# jupiter6-filter.net
KiCad netlist of a schematic drawn in EAGLE
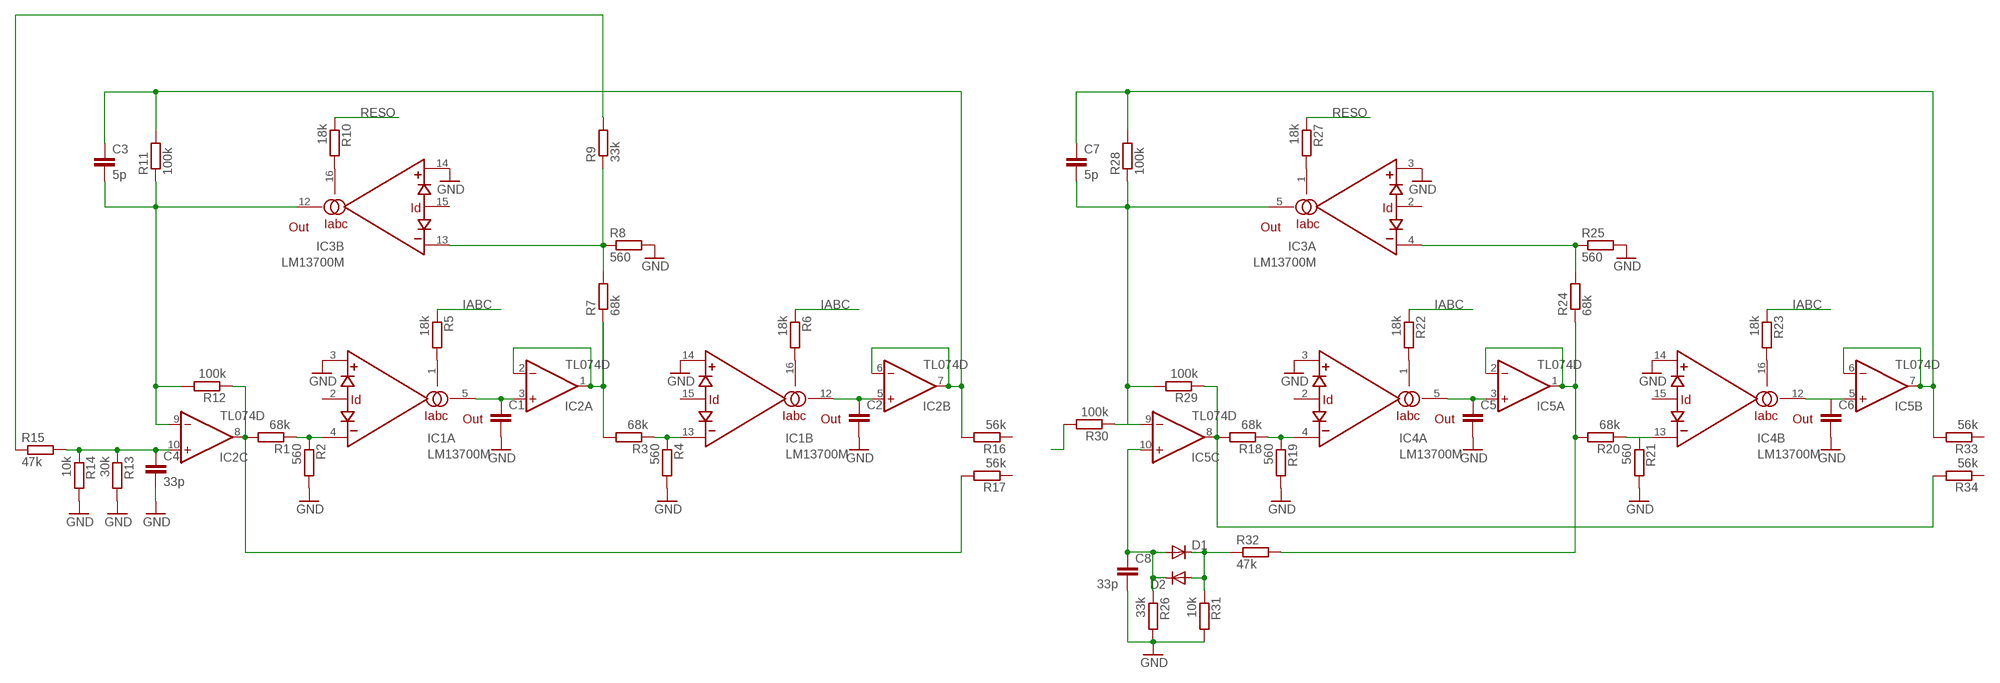
[diagram p0: schematic, sheet 1]

(export (version "E")
  (design (tool "Eeschema 10.0.6"))
  (components
    (comp (ref "C1")
      (value "C-EUC0603")
      (footprint "eagle-import:C0603")
      (libsource (lib "eagle-import") (part "C-EUC0603"))
    )
    (comp (ref "C2")
      (value "C-EUC0603")
      (footprint "eagle-import:C0603")
      (libsource (lib "eagle-import") (part "C-EUC0603"))
    )
    (comp (ref "C3")
      (value "5p")
      (footprint "eagle-import:C0603")
      (libsource (lib "eagle-import") (part "C-EUC0603"))
    )
    (comp (ref "C4")
      (value "33p")
      (footprint "eagle-import:C0603")
      (libsource (lib "eagle-import") (part "C-EUC0603"))
    )
    (comp (ref "C5")
      (value "C-EUC0603")
      (footprint "eagle-import:C0603")
      (libsource (lib "eagle-import") (part "C-EUC0603"))
    )
    (comp (ref "C6")
      (value "C-EUC0603")
      (footprint "eagle-import:C0603")
      (libsource (lib "eagle-import") (part "C-EUC0603"))
    )
    (comp (ref "C7")
      (value "5p")
      (footprint "eagle-import:C0603")
      (libsource (lib "eagle-import") (part "C-EUC0603"))
    )
    (comp (ref "C8")
      (value "33p")
      (footprint "eagle-import:C0603")
      (libsource (lib "eagle-import") (part "C-EUC0603"))
    )
    (comp (ref "D1")
      (value "DIODE-SOD80C")
      (footprint "eagle-import:SOD80C")
      (libsource (lib "eagle-import") (part "DIODE-SOD80C"))
    )
    (comp (ref "D2")
      (value "DIODE-SOD80C")
      (footprint "eagle-import:SOD80C")
      (libsource (lib "eagle-import") (part "DIODE-SOD80C"))
    )
    (comp (ref "IC1")
      (value "LM13700M")
      (footprint "eagle-import:SO16")
      (libsource (lib "eagle-import") (part "LM13700M"))
    )
    (comp (ref "IC2")
      (value "TL074D")
      (footprint "eagle-import:SO14")
      (libsource (lib "eagle-import") (part "TL074D"))
    )
    (comp (ref "IC3")
      (value "LM13700M")
      (footprint "eagle-import:SO16")
      (libsource (lib "eagle-import") (part "LM13700M"))
    )
    (comp (ref "IC4")
      (value "LM13700M")
      (footprint "eagle-import:SO16")
      (libsource (lib "eagle-import") (part "LM13700M"))
    )
    (comp (ref "IC5")
      (value "TL074D")
      (footprint "eagle-import:SO14")
      (libsource (lib "eagle-import") (part "TL074D"))
    )
    (comp (ref "R1")
      (value "68k")
      (footprint "eagle-import:R0603")
      (libsource (lib "eagle-import") (part "R-EU_R0603"))
    )
    (comp (ref "R2")
      (value "560")
      (footprint "eagle-import:R0603")
      (libsource (lib "eagle-import") (part "R-EU_R0603"))
    )
    (comp (ref "R3")
      (value "68k")
      (footprint "eagle-import:R0603")
      (libsource (lib "eagle-import") (part "R-EU_R0603"))
    )
    (comp (ref "R4")
      (value "560")
      (footprint "eagle-import:R0603")
      (libsource (lib "eagle-import") (part "R-EU_R0603"))
    )
    (comp (ref "R5")
      (value "18k")
      (footprint "eagle-import:R0603")
      (libsource (lib "eagle-import") (part "R-EU_R0603"))
    )
    (comp (ref "R6")
      (value "18k")
      (footprint "eagle-import:R0603")
      (libsource (lib "eagle-import") (part "R-EU_R0603"))
    )
    (comp (ref "R7")
      (value "68k")
      (footprint "eagle-import:R0603")
      (libsource (lib "eagle-import") (part "R-EU_R0603"))
    )
    (comp (ref "R8")
      (value "560")
      (footprint "eagle-import:R0603")
      (libsource (lib "eagle-import") (part "R-EU_R0603"))
    )
    (comp (ref "R9")
      (value "33k")
      (footprint "eagle-import:R0603")
      (libsource (lib "eagle-import") (part "R-EU_R0603"))
    )
    (comp (ref "R10")
      (value "18k")
      (footprint "eagle-import:R0603")
      (libsource (lib "eagle-import") (part "R-EU_R0603"))
    )
    (comp (ref "R11")
      (value "100k")
      (footprint "eagle-import:R0603")
      (libsource (lib "eagle-import") (part "R-EU_R0603"))
    )
    (comp (ref "R12")
      (value "100k")
      (footprint "eagle-import:R0603")
      (libsource (lib "eagle-import") (part "R-EU_R0603"))
    )
    (comp (ref "R13")
      (value "30k")
      (footprint "eagle-import:R0603")
      (libsource (lib "eagle-import") (part "R-EU_R0603"))
    )
    (comp (ref "R14")
      (value "10k")
      (footprint "eagle-import:R0603")
      (libsource (lib "eagle-import") (part "R-EU_R0603"))
    )
    (comp (ref "R15")
      (value "47k")
      (footprint "eagle-import:R0603")
      (libsource (lib "eagle-import") (part "R-EU_R0603"))
    )
    (comp (ref "R16")
      (value "56k")
      (footprint "eagle-import:R0603")
      (libsource (lib "eagle-import") (part "R-EU_R0603"))
    )
    (comp (ref "R17")
      (value "56k")
      (footprint "eagle-import:R0603")
      (libsource (lib "eagle-import") (part "R-EU_R0603"))
    )
    (comp (ref "R18")
      (value "68k")
      (footprint "eagle-import:R0603")
      (libsource (lib "eagle-import") (part "R-EU_R0603"))
    )
    (comp (ref "R19")
      (value "560")
      (footprint "eagle-import:R0603")
      (libsource (lib "eagle-import") (part "R-EU_R0603"))
    )
    (comp (ref "R20")
      (value "68k")
      (footprint "eagle-import:R0603")
      (libsource (lib "eagle-import") (part "R-EU_R0603"))
    )
    (comp (ref "R21")
      (value "560")
      (footprint "eagle-import:R0603")
      (libsource (lib "eagle-import") (part "R-EU_R0603"))
    )
    (comp (ref "R22")
      (value "18k")
      (footprint "eagle-import:R0603")
      (libsource (lib "eagle-import") (part "R-EU_R0603"))
    )
    (comp (ref "R23")
      (value "18k")
      (footprint "eagle-import:R0603")
      (libsource (lib "eagle-import") (part "R-EU_R0603"))
    )
    (comp (ref "R24")
      (value "68k")
      (footprint "eagle-import:R0603")
      (libsource (lib "eagle-import") (part "R-EU_R0603"))
    )
    (comp (ref "R25")
      (value "560")
      (footprint "eagle-import:R0603")
      (libsource (lib "eagle-import") (part "R-EU_R0603"))
    )
    (comp (ref "R26")
      (value "33k")
      (footprint "eagle-import:R0603")
      (libsource (lib "eagle-import") (part "R-EU_R0603"))
    )
    (comp (ref "R27")
      (value "18k")
      (footprint "eagle-import:R0603")
      (libsource (lib "eagle-import") (part "R-EU_R0603"))
    )
    (comp (ref "R28")
      (value "100k")
      (footprint "eagle-import:R0603")
      (libsource (lib "eagle-import") (part "R-EU_R0603"))
    )
    (comp (ref "R29")
      (value "100k")
      (footprint "eagle-import:R0603")
      (libsource (lib "eagle-import") (part "R-EU_R0603"))
    )
    (comp (ref "R30")
      (value "100k")
      (footprint "eagle-import:R0603")
      (libsource (lib "eagle-import") (part "R-EU_R0603"))
    )
    (comp (ref "R31")
      (value "10k")
      (footprint "eagle-import:R0603")
      (libsource (lib "eagle-import") (part "R-EU_R0603"))
    )
    (comp (ref "R32")
      (value "47k")
      (footprint "eagle-import:R0603")
      (libsource (lib "eagle-import") (part "R-EU_R0603"))
    )
    (comp (ref "R33")
      (value "56k")
      (footprint "eagle-import:R0603")
      (libsource (lib "eagle-import") (part "R-EU_R0603"))
    )
    (comp (ref "R34")
      (value "56k")
      (footprint "eagle-import:R0603")
      (libsource (lib "eagle-import") (part "R-EU_R0603"))
    )
  )
  (nets
    (net (code "1") (name "/IABC") (class "Default")
      (node (ref "R22") (pin "1") (pinfunction "1_1") (pintype "passive"))
      (node (ref "R23") (pin "1") (pinfunction "1_1") (pintype "passive"))
      (node (ref "R5") (pin "1") (pinfunction "1_1") (pintype "passive"))
      (node (ref "R6") (pin "1") (pinfunction "1_1") (pintype "passive"))
    )
    (net (code "2") (name "/RESO") (class "Default")
      (node (ref "R10") (pin "1") (pinfunction "1_1") (pintype "passive"))
      (node (ref "R27") (pin "1") (pinfunction "1_1") (pintype "passive"))
    )
    (net (code "3") (name "GND") (class "Default")
      (node (ref "C1") (pin "2") (pinfunction "2_2") (pintype "passive"))
      (node (ref "C2") (pin "2") (pinfunction "2_2") (pintype "passive"))
      (node (ref "C4") (pin "2") (pinfunction "2_2") (pintype "passive"))
      (node (ref "C5") (pin "2") (pinfunction "2_2") (pintype "passive"))
      (node (ref "C6") (pin "2") (pinfunction "2_2") (pintype "passive"))
      (node (ref "C8") (pin "2") (pinfunction "2_2") (pintype "passive"))
      (node (ref "IC1") (pin "14") (pinfunction "+IN_14") (pintype "bidirectional"))
      (node (ref "IC1") (pin "3") (pinfunction "+IN_3") (pintype "bidirectional"))
      (node (ref "IC3") (pin "14") (pinfunction "+IN_14") (pintype "bidirectional"))
      (node (ref "IC3") (pin "3") (pinfunction "+IN_3") (pintype "bidirectional"))
      (node (ref "IC4") (pin "14") (pinfunction "+IN_14") (pintype "bidirectional"))
      (node (ref "IC4") (pin "3") (pinfunction "+IN_3") (pintype "bidirectional"))
      (node (ref "R13") (pin "2") (pinfunction "2_2") (pintype "passive"))
      (node (ref "R14") (pin "2") (pinfunction "2_2") (pintype "passive"))
      (node (ref "R19") (pin "2") (pinfunction "2_2") (pintype "passive"))
      (node (ref "R2") (pin "2") (pinfunction "2_2") (pintype "passive"))
      (node (ref "R21") (pin "2") (pinfunction "2_2") (pintype "passive"))
      (node (ref "R25") (pin "2") (pinfunction "2_2") (pintype "passive"))
      (node (ref "R26") (pin "2") (pinfunction "2_2") (pintype "passive"))
      (node (ref "R31") (pin "2") (pinfunction "2_2") (pintype "passive"))
      (node (ref "R4") (pin "2") (pinfunction "2_2") (pintype "passive"))
      (node (ref "R8") (pin "2") (pinfunction "2_2") (pintype "passive"))
    )
    (net (code "4") (name "Net-(D1-PadC)") (class "Default")
      (node (ref "D1") (pin "C") (pinfunction "C_C") (pintype "passive"))
      (node (ref "D2") (pin "A") (pinfunction "A_A") (pintype "passive"))
      (node (ref "R31") (pin "1") (pinfunction "1_1") (pintype "passive"))
      (node (ref "R32") (pin "1") (pinfunction "1_1") (pintype "passive"))
    )
    (net (code "5") (name "Net-(IC1A--IN)") (class "Default")
      (node (ref "IC1") (pin "4") (pinfunction "-IN_4") (pintype "bidirectional"))
      (node (ref "R1") (pin "1") (pinfunction "1_1") (pintype "passive"))
      (node (ref "R2") (pin "1") (pinfunction "1_1") (pintype "passive"))
    )
    (net (code "6") (name "Net-(IC1A-IABC)") (class "Default")
      (node (ref "IC1") (pin "1") (pinfunction "IABC_1") (pintype "bidirectional"))
      (node (ref "R5") (pin "2") (pinfunction "2_2") (pintype "passive"))
    )
    (net (code "7") (name "Net-(IC1A-OUT)") (class "Default")
      (node (ref "C1") (pin "1") (pinfunction "1_1") (pintype "passive"))
      (node (ref "IC1") (pin "5") (pinfunction "OUT_5") (pintype "bidirectional"))
      (node (ref "IC2") (pin "3") (pinfunction "+IN_3") (pintype "input"))
    )
    (net (code "8") (name "Net-(IC1B--IN)") (class "Default")
      (node (ref "IC1") (pin "13") (pinfunction "-IN_13") (pintype "bidirectional"))
      (node (ref "R3") (pin "1") (pinfunction "1_1") (pintype "passive"))
      (node (ref "R4") (pin "1") (pinfunction "1_1") (pintype "passive"))
    )
    (net (code "9") (name "Net-(IC1B-IABC)") (class "Default")
      (node (ref "IC1") (pin "16") (pinfunction "IABC_16") (pintype "bidirectional"))
      (node (ref "R6") (pin "2") (pinfunction "2_2") (pintype "passive"))
    )
    (net (code "10") (name "Net-(IC1B-OUT)") (class "Default")
      (node (ref "C2") (pin "1") (pinfunction "1_1") (pintype "passive"))
      (node (ref "IC1") (pin "12") (pinfunction "OUT_12") (pintype "bidirectional"))
      (node (ref "IC2") (pin "5") (pinfunction "+IN_5") (pintype "input"))
    )
    (net (code "11") (name "Net-(IC2A--IN)") (class "Default")
      (node (ref "IC2") (pin "1") (pinfunction "OUT_1") (pintype "output"))
      (node (ref "IC2") (pin "2") (pinfunction "-IN_2") (pintype "input"))
      (node (ref "R3") (pin "2") (pinfunction "2_2") (pintype "passive"))
      (node (ref "R7") (pin "1") (pinfunction "1_1") (pintype "passive"))
    )
    (net (code "12") (name "Net-(IC2B--IN)") (class "Default")
      (node (ref "C3") (pin "1") (pinfunction "1_1") (pintype "passive"))
      (node (ref "IC2") (pin "6") (pinfunction "-IN_6") (pintype "input"))
      (node (ref "IC2") (pin "7") (pinfunction "OUT_7") (pintype "output"))
      (node (ref "R11") (pin "2") (pinfunction "2_2") (pintype "passive"))
      (node (ref "R16") (pin "2") (pinfunction "2_2") (pintype "passive"))
    )
    (net (code "13") (name "Net-(IC2C-+IN)") (class "Default")
      (node (ref "C4") (pin "1") (pinfunction "1_1") (pintype "passive"))
      (node (ref "IC2") (pin "10") (pinfunction "+IN_10") (pintype "input"))
      (node (ref "R13") (pin "1") (pinfunction "1_1") (pintype "passive"))
      (node (ref "R14") (pin "1") (pinfunction "1_1") (pintype "passive"))
      (node (ref "R15") (pin "2") (pinfunction "2_2") (pintype "passive"))
    )
    (net (code "14") (name "Net-(IC2C--IN)") (class "Default")
      (node (ref "C3") (pin "2") (pinfunction "2_2") (pintype "passive"))
      (node (ref "IC2") (pin "9") (pinfunction "-IN_9") (pintype "input"))
      (node (ref "IC3") (pin "12") (pinfunction "OUT_12") (pintype "bidirectional"))
      (node (ref "R11") (pin "1") (pinfunction "1_1") (pintype "passive"))
      (node (ref "R12") (pin "2") (pinfunction "2_2") (pintype "passive"))
    )
    (net (code "15") (name "Net-(IC2C-OUT)") (class "Default")
      (node (ref "IC2") (pin "8") (pinfunction "OUT_8") (pintype "output"))
      (node (ref "R1") (pin "2") (pinfunction "2_2") (pintype "passive"))
      (node (ref "R12") (pin "1") (pinfunction "1_1") (pintype "passive"))
      (node (ref "R17") (pin "2") (pinfunction "2_2") (pintype "passive"))
    )
    (net (code "16") (name "Net-(IC3A--IN)") (class "Default")
      (node (ref "IC3") (pin "4") (pinfunction "-IN_4") (pintype "bidirectional"))
      (node (ref "R24") (pin "2") (pinfunction "2_2") (pintype "passive"))
      (node (ref "R25") (pin "1") (pinfunction "1_1") (pintype "passive"))
    )
    (net (code "17") (name "Net-(IC3A-IABC)") (class "Default")
      (node (ref "IC3") (pin "1") (pinfunction "IABC_1") (pintype "bidirectional"))
      (node (ref "R27") (pin "2") (pinfunction "2_2") (pintype "passive"))
    )
    (net (code "18") (name "Net-(IC3A-OUT)") (class "Default")
      (node (ref "C7") (pin "2") (pinfunction "2_2") (pintype "passive"))
      (node (ref "IC3") (pin "5") (pinfunction "OUT_5") (pintype "bidirectional"))
      (node (ref "IC5") (pin "9") (pinfunction "-IN_9") (pintype "input"))
      (node (ref "R28") (pin "1") (pinfunction "1_1") (pintype "passive"))
      (node (ref "R29") (pin "2") (pinfunction "2_2") (pintype "passive"))
      (node (ref "R30") (pin "1") (pinfunction "1_1") (pintype "passive"))
    )
    (net (code "19") (name "Net-(IC3B--IN)") (class "Default")
      (node (ref "IC3") (pin "13") (pinfunction "-IN_13") (pintype "bidirectional"))
      (node (ref "R7") (pin "2") (pinfunction "2_2") (pintype "passive"))
      (node (ref "R8") (pin "1") (pinfunction "1_1") (pintype "passive"))
      (node (ref "R9") (pin "1") (pinfunction "1_1") (pintype "passive"))
    )
    (net (code "20") (name "Net-(IC3B-IABC)") (class "Default")
      (node (ref "IC3") (pin "16") (pinfunction "IABC_16") (pintype "bidirectional"))
      (node (ref "R10") (pin "2") (pinfunction "2_2") (pintype "passive"))
    )
    (net (code "21") (name "Net-(IC4A--IN)") (class "Default")
      (node (ref "IC4") (pin "4") (pinfunction "-IN_4") (pintype "bidirectional"))
      (node (ref "R18") (pin "1") (pinfunction "1_1") (pintype "passive"))
      (node (ref "R19") (pin "1") (pinfunction "1_1") (pintype "passive"))
    )
    (net (code "22") (name "Net-(IC4A-IABC)") (class "Default")
      (node (ref "IC4") (pin "1") (pinfunction "IABC_1") (pintype "bidirectional"))
      (node (ref "R22") (pin "2") (pinfunction "2_2") (pintype "passive"))
    )
    (net (code "23") (name "Net-(IC4A-OUT)") (class "Default")
      (node (ref "C5") (pin "1") (pinfunction "1_1") (pintype "passive"))
      (node (ref "IC4") (pin "5") (pinfunction "OUT_5") (pintype "bidirectional"))
      (node (ref "IC5") (pin "3") (pinfunction "+IN_3") (pintype "input"))
    )
    (net (code "24") (name "Net-(IC4B--IN)") (class "Default")
      (node (ref "IC4") (pin "13") (pinfunction "-IN_13") (pintype "bidirectional"))
      (node (ref "R20") (pin "1") (pinfunction "1_1") (pintype "passive"))
      (node (ref "R21") (pin "1") (pinfunction "1_1") (pintype "passive"))
    )
    (net (code "25") (name "Net-(IC4B-IABC)") (class "Default")
      (node (ref "IC4") (pin "16") (pinfunction "IABC_16") (pintype "bidirectional"))
      (node (ref "R23") (pin "2") (pinfunction "2_2") (pintype "passive"))
    )
    (net (code "26") (name "Net-(IC4B-OUT)") (class "Default")
      (node (ref "C6") (pin "1") (pinfunction "1_1") (pintype "passive"))
      (node (ref "IC4") (pin "12") (pinfunction "OUT_12") (pintype "bidirectional"))
      (node (ref "IC5") (pin "5") (pinfunction "+IN_5") (pintype "input"))
    )
    (net (code "27") (name "Net-(IC5A--IN)") (class "Default")
      (node (ref "IC5") (pin "1") (pinfunction "OUT_1") (pintype "output"))
      (node (ref "IC5") (pin "2") (pinfunction "-IN_2") (pintype "input"))
      (node (ref "R20") (pin "2") (pinfunction "2_2") (pintype "passive"))
      (node (ref "R24") (pin "1") (pinfunction "1_1") (pintype "passive"))
      (node (ref "R32") (pin "2") (pinfunction "2_2") (pintype "passive"))
    )
    (net (code "28") (name "Net-(IC5B--IN)") (class "Default")
      (node (ref "C7") (pin "1") (pinfunction "1_1") (pintype "passive"))
      (node (ref "IC5") (pin "6") (pinfunction "-IN_6") (pintype "input"))
      (node (ref "IC5") (pin "7") (pinfunction "OUT_7") (pintype "output"))
      (node (ref "R28") (pin "2") (pinfunction "2_2") (pintype "passive"))
      (node (ref "R33") (pin "2") (pinfunction "2_2") (pintype "passive"))
    )
    (net (code "29") (name "Net-(IC5C-+IN)") (class "Default")
      (node (ref "C8") (pin "1") (pinfunction "1_1") (pintype "passive"))
      (node (ref "D1") (pin "A") (pinfunction "A_A") (pintype "passive"))
      (node (ref "D2") (pin "C") (pinfunction "C_C") (pintype "passive"))
      (node (ref "IC5") (pin "10") (pinfunction "+IN_10") (pintype "input"))
      (node (ref "R26") (pin "1") (pinfunction "1_1") (pintype "passive"))
    )
    (net (code "30") (name "Net-(IC5C-OUT)") (class "Default")
      (node (ref "IC5") (pin "8") (pinfunction "OUT_8") (pintype "output"))
      (node (ref "R18") (pin "2") (pinfunction "2_2") (pintype "passive"))
      (node (ref "R29") (pin "1") (pinfunction "1_1") (pintype "passive"))
      (node (ref "R34") (pin "2") (pinfunction "2_2") (pintype "passive"))
    )
    (net (code "31") (name "Net-(R15-Pad1)") (class "Default")
      (node (ref "R15") (pin "1") (pinfunction "1_1") (pintype "passive"))
      (node (ref "R9") (pin "2") (pinfunction "2_2") (pintype "passive"))
    )
    (net (code "32") (name "unconnected-(IC1A-ID-Pad2)") (class "Default")
      (node (ref "IC1") (pin "2") (pinfunction "ID_2") (pintype "bidirectional"))
    )
    (net (code "33") (name "unconnected-(IC1B-ID-Pad15)") (class "Default")
      (node (ref "IC1") (pin "15") (pinfunction "ID_15") (pintype "bidirectional"))
    )
    (net (code "34") (name "unconnected-(IC3A-ID-Pad2)") (class "Default")
      (node (ref "IC3") (pin "2") (pinfunction "ID_2") (pintype "bidirectional"))
    )
    (net (code "35") (name "unconnected-(IC3B-ID-Pad15)") (class "Default")
      (node (ref "IC3") (pin "15") (pinfunction "ID_15") (pintype "bidirectional"))
    )
    (net (code "36") (name "unconnected-(IC4A-ID-Pad2)") (class "Default")
      (node (ref "IC4") (pin "2") (pinfunction "ID_2") (pintype "bidirectional"))
    )
    (net (code "37") (name "unconnected-(IC4B-ID-Pad15)") (class "Default")
      (node (ref "IC4") (pin "15") (pinfunction "ID_15") (pintype "bidirectional"))
    )
    (net (code "38") (name "unconnected-(R16-Pad1)") (class "Default")
      (node (ref "R16") (pin "1") (pinfunction "1_1") (pintype "passive"))
    )
    (net (code "39") (name "unconnected-(R17-Pad1)") (class "Default")
      (node (ref "R17") (pin "1") (pinfunction "1_1") (pintype "passive"))
    )
    (net (code "40") (name "unconnected-(R30-Pad2)") (class "Default")
      (node (ref "R30") (pin "2") (pinfunction "2_2") (pintype "passive"))
    )
    (net (code "41") (name "unconnected-(R33-Pad1)") (class "Default")
      (node (ref "R33") (pin "1") (pinfunction "1_1") (pintype "passive"))
    )
    (net (code "42") (name "unconnected-(R34-Pad1)") (class "Default")
      (node (ref "R34") (pin "1") (pinfunction "1_1") (pintype "passive"))
    )
  )
)
